# BBB_Headers.net
KiCad netlist of a schematic drawn in Altium Designer
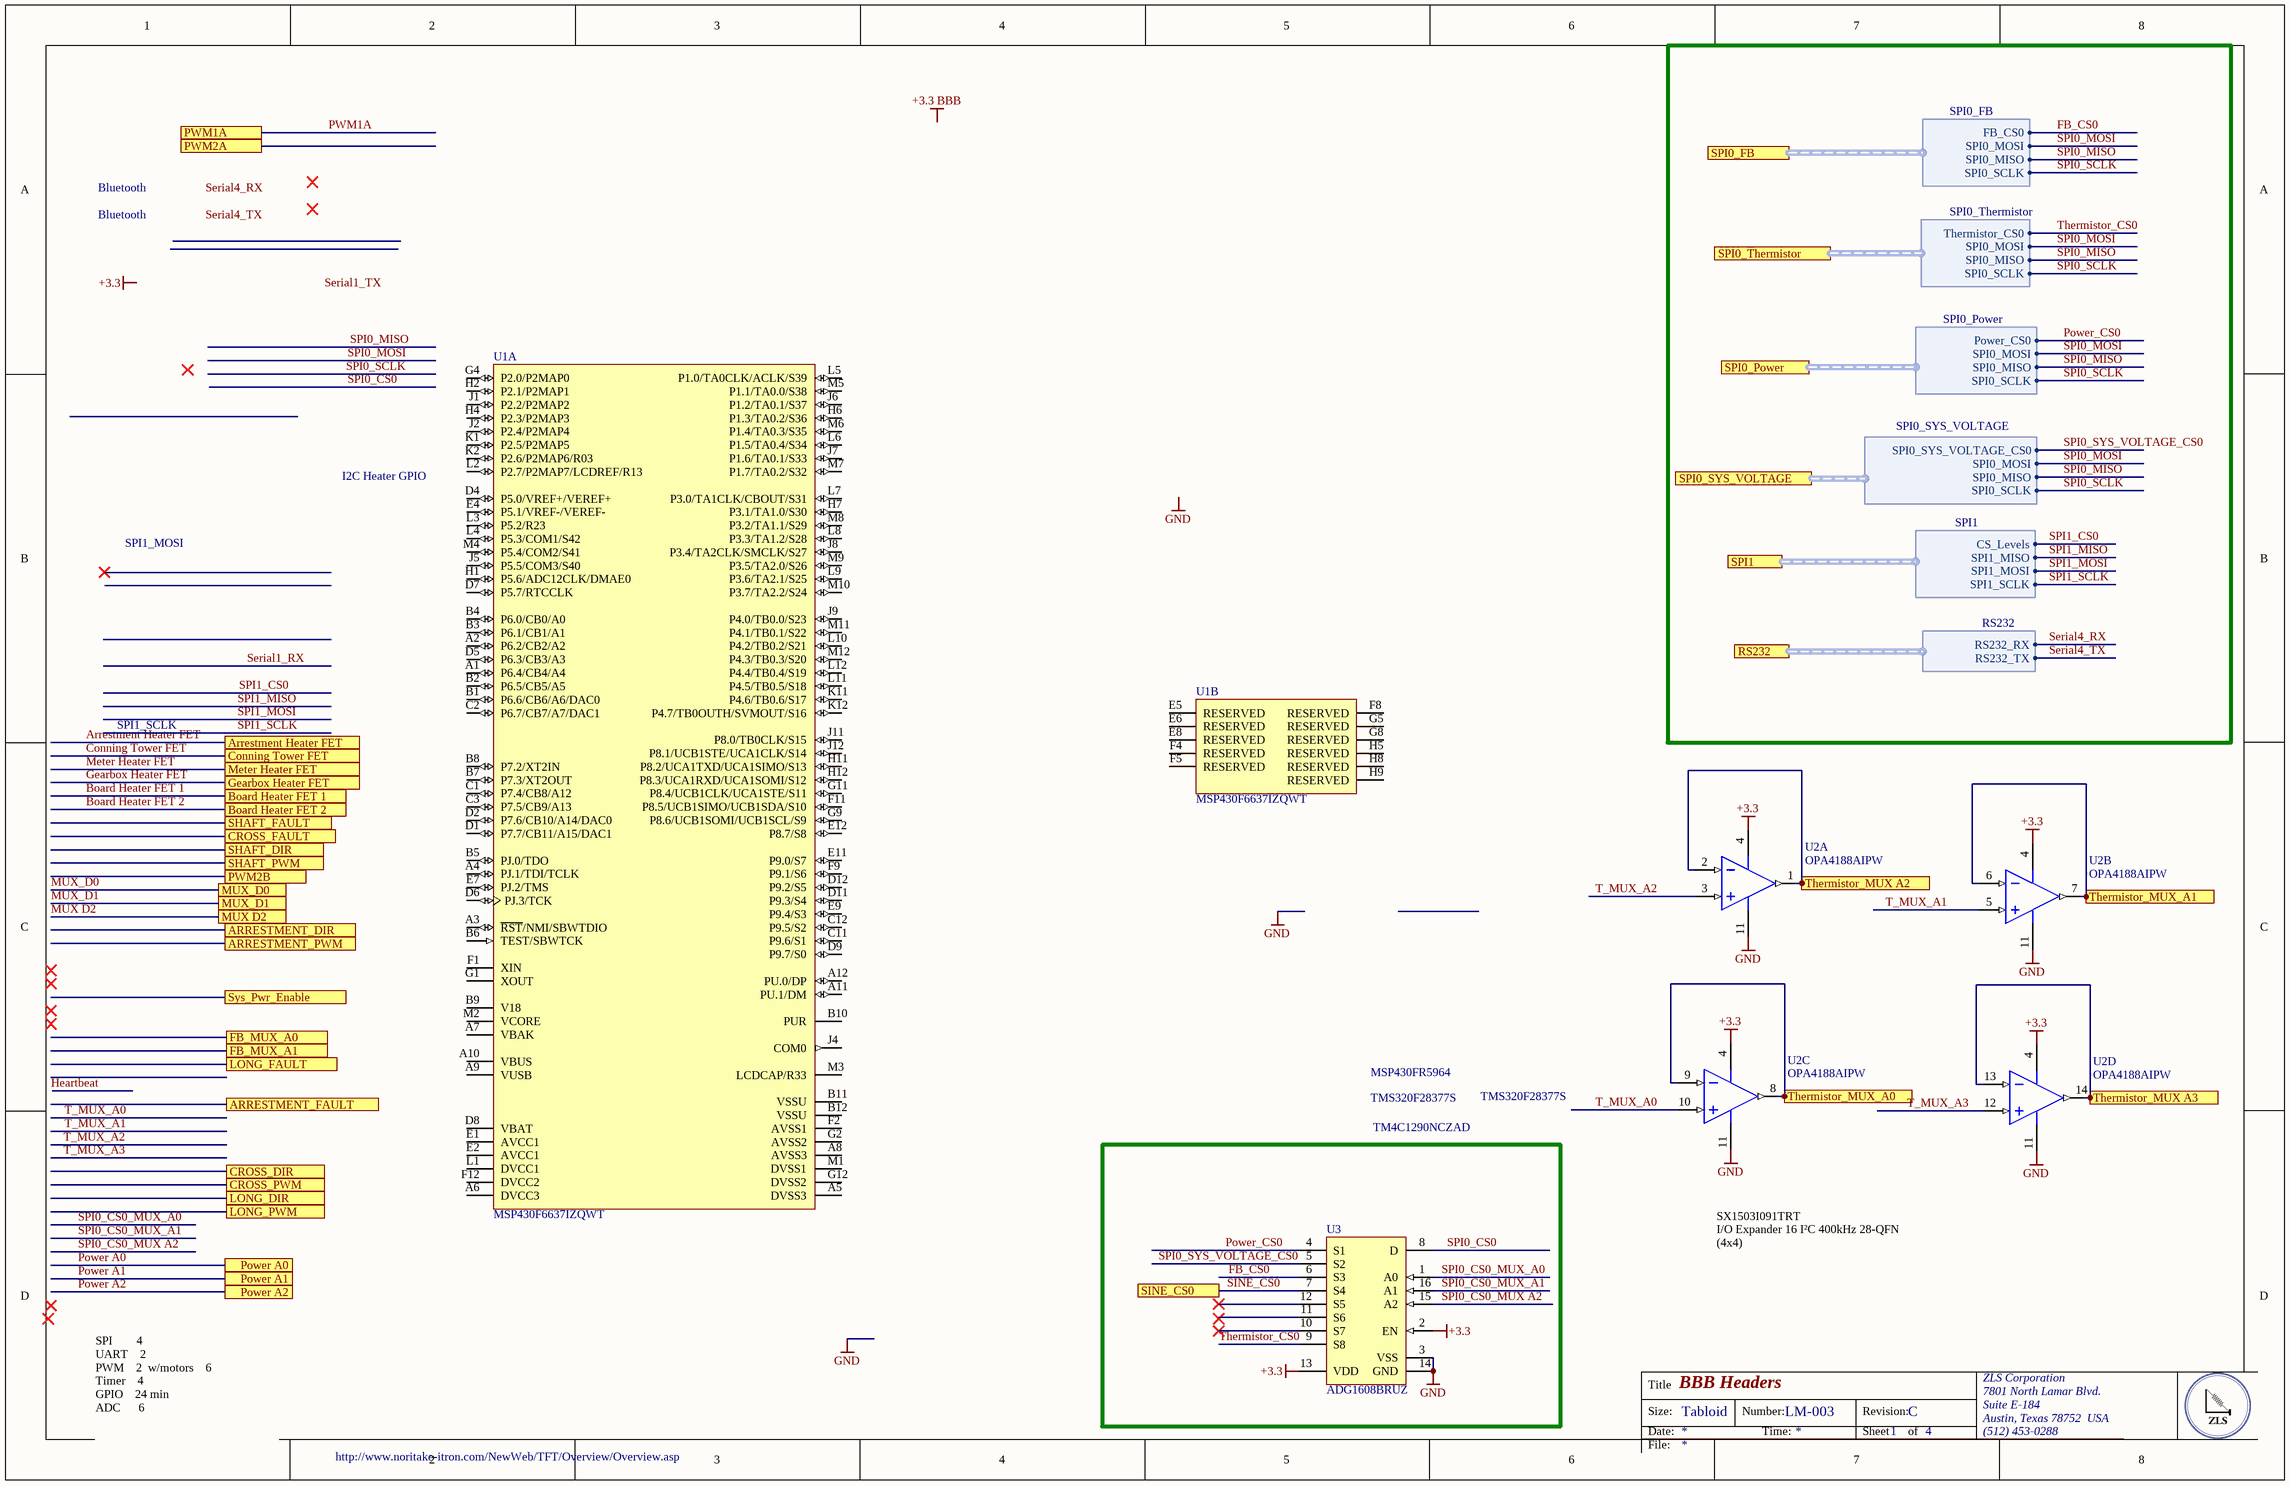
[diagram p0: BBB Headers.SchDoc]

(export (version "E")
  (design (tool "Eeschema 10.0.6"))
  (components
    (comp (ref "U1")
      (value "MSP430F6637IZQWT")
      (footprint "TI-ZQW113")
      (fields (field (name "MANUFACTURER") "Texas Instruments"))
      (libsource (lib "Altium Content Vault") (part "TI-MSP430F663X-ZQW113_A"))
    )
    (comp (ref "U2")
      (value "OPA4188AIPW")
      (footprint "PW0014A_N")
      (fields (field (name "MANUFACTURER") "Texas Instruments"))
      (libsource (lib "Altium Content Vault") (part "TI-OPA4188-PW14"))
    )
    (comp (ref "U3")
      (value "ADG1608BRUZ")
      (footprint "ADI-RU-16_M")
      (description "4.5 Ohm Ron, 8-Channel +/-5 V,+12 V, +5 V and +3.3 V Multiplexer, 16-pin SOP (RU-16), Tube")
      (fields (field (name "MANUFACTURER") "Analog Devices Inc.") (field (name "BASE PART NUMBER") "ADG1608"))
      (libsource (lib "Altium Content Vault") (part "CMP-0793-00136-1"))
    )
  )
  (nets
    (net (code "7") (name "+3.3") (class "Default")
      (node (ref "U2") (pin "4") (pinfunction "V+_4") (pintype "power_in"))
      (node (ref "U3") (pin "13") (pinfunction "VDD_13") (pintype "power_in"))
      (node (ref "U3") (pin "2") (pinfunction "EN_2") (pintype "input"))
    )
    (net (code "19") (name "/FB_CS0") (class "Default")
      (node (ref "U3") (pin "6") (pinfunction "S3_6") (pintype "passive"))
    )
    (net (code "37") (name "/Power_CS0") (class "Default")
      (node (ref "U3") (pin "4") (pinfunction "S1_4") (pintype "passive"))
    )
    (net (code "41") (name "/SINE_CS0") (class "Default")
      (node (ref "U3") (pin "7") (pinfunction "S4_7") (pintype "passive"))
    )
    (net (code "42") (name "/SPI0_CS0") (class "Default")
      (node (ref "U3") (pin "8") (pinfunction "D_8") (pintype "passive"))
    )
    (net (code "43") (name "/SPI0_CS0_MUX A2") (class "Default")
      (node (ref "U3") (pin "15") (pinfunction "A2_15") (pintype "input"))
    )
    (net (code "44") (name "/SPI0_CS0_MUX_A0") (class "Default")
      (node (ref "U3") (pin "1") (pinfunction "A0_1") (pintype "input"))
    )
    (net (code "45") (name "/SPI0_CS0_MUX_A1") (class "Default")
      (node (ref "U3") (pin "16") (pinfunction "A1_16") (pintype "input"))
    )
    (net (code "49") (name "/SPI0_SYS_VOLTAGE_CS0") (class "Default")
      (node (ref "U3") (pin "5") (pinfunction "S2_5") (pintype "passive"))
    )
    (net (code "59") (name "/T_MUX_A0") (class "Default")
      (node (ref "U2") (pin "10") (pinfunction "IN_C+_10") (pintype "input"))
    )
    (net (code "60") (name "/T_MUX_A1") (class "Default")
      (node (ref "U2") (pin "5") (pinfunction "IN_B+_5") (pintype "input"))
    )
    (net (code "61") (name "/T_MUX_A2") (class "Default")
      (node (ref "U2") (pin "3") (pinfunction "IN_A+_3") (pintype "input"))
    )
    (net (code "62") (name "/T_MUX_A3") (class "Default")
      (node (ref "U2") (pin "12") (pinfunction "IN_D+_12") (pintype "input"))
    )
    (net (code "63") (name "/Thermistor_CS0") (class "Default")
      (node (ref "U3") (pin "9") (pinfunction "S8_9") (pintype "passive"))
    )
    (net (code "64") (name "/Thermistor_MUX A2") (class "Default")
      (node (ref "U2") (pin "1") (pinfunction "OUT_A_1") (pintype "output"))
      (node (ref "U2") (pin "2") (pinfunction "IN_A-_2") (pintype "input"))
    )
    (net (code "65") (name "/Thermistor_MUX A3") (class "Default")
      (node (ref "U2") (pin "13") (pinfunction "IN_D-_13") (pintype "input"))
      (node (ref "U2") (pin "14") (pinfunction "OUT_D_14") (pintype "output"))
    )
    (net (code "66") (name "/Thermistor_MUX_A0") (class "Default")
      (node (ref "U2") (pin "8") (pinfunction "OUT_C_8") (pintype "output"))
      (node (ref "U2") (pin "9") (pinfunction "IN_C-_9") (pintype "input"))
    )
    (net (code "67") (name "/Thermistor_MUX_A1") (class "Default")
      (node (ref "U2") (pin "6") (pinfunction "IN_B-_6") (pintype "input"))
      (node (ref "U2") (pin "7") (pinfunction "OUT_B_7") (pintype "output"))
    )
    (net (code "74") (name "GND") (class "Default")
      (node (ref "U2") (pin "11") (pinfunction "V-_11") (pintype "power_in"))
      (node (ref "U3") (pin "14") (pinfunction "GND_14") (pintype "power_in"))
      (node (ref "U3") (pin "3") (pinfunction "VSS_3") (pintype "power_in"))
    )
    (net (code "75") (name "unconnected-(U1A-AVCC1-PadE1)") (class "Default")
      (node (ref "U1") (pin "E1") (pinfunction "AVCC1_E1") (pintype "power_in"))
    )
    (net (code "76") (name "unconnected-(U1A-AVCC1-PadE2)") (class "Default")
      (node (ref "U1") (pin "E2") (pinfunction "AVCC1_E2") (pintype "power_in"))
    )
    (net (code "77") (name "unconnected-(U1A-AVSS1-PadF2)") (class "Default")
      (node (ref "U1") (pin "F2") (pinfunction "AVSS1_F2") (pintype "power_in"))
    )
    (net (code "78") (name "unconnected-(U1A-AVSS2-PadG2)") (class "Default")
      (node (ref "U1") (pin "G2") (pinfunction "AVSS2_G2") (pintype "power_in"))
    )
    (net (code "79") (name "unconnected-(U1A-AVSS3-PadA8)") (class "Default")
      (node (ref "U1") (pin "A8") (pinfunction "AVSS3_A8") (pintype "power_in"))
    )
    (net (code "80") (name "unconnected-(U1A-COM0-PadJ4)") (class "Default")
      (node (ref "U1") (pin "J4") (pinfunction "COM0_J4") (pintype "output"))
    )
    (net (code "81") (name "unconnected-(U1A-DVCC1-PadL1)") (class "Default")
      (node (ref "U1") (pin "L1") (pinfunction "DVCC1_L1") (pintype "power_in"))
    )
    (net (code "82") (name "unconnected-(U1A-DVCC2-PadF12)") (class "Default")
      (node (ref "U1") (pin "F12") (pinfunction "DVCC2_F12") (pintype "power_in"))
    )
    (net (code "83") (name "unconnected-(U1A-DVCC3-PadA6)") (class "Default")
      (node (ref "U1") (pin "A6") (pinfunction "DVCC3_A6") (pintype "power_in"))
    )
    (net (code "84") (name "unconnected-(U1A-DVSS1-PadM1)") (class "Default")
      (node (ref "U1") (pin "M1") (pinfunction "DVSS1_M1") (pintype "power_in"))
    )
    (net (code "85") (name "unconnected-(U1A-DVSS2-PadG12)") (class "Default")
      (node (ref "U1") (pin "G12") (pinfunction "DVSS2_G12") (pintype "power_in"))
    )
    (net (code "86") (name "unconnected-(U1A-DVSS3-PadA5)") (class "Default")
      (node (ref "U1") (pin "A5") (pinfunction "DVSS3_A5") (pintype "power_in"))
    )
    (net (code "87") (name "unconnected-(U1A-LCDCAP{slash}R33-PadM3)") (class "Default")
      (node (ref "U1") (pin "M3") (pinfunction "LCDCAP/R33_M3") (pintype "passive"))
    )
    (net (code "88") (name "unconnected-(U1A-P1.0{slash}TA0CLK{slash}ACLK{slash}S39-PadL5)") (class "Default")
      (node (ref "U1") (pin "L5") (pinfunction "P1.0/TA0CLK/ACLK/S39_L5") (pintype "bidirectional"))
    )
    (net (code "89") (name "unconnected-(U1A-P1.1{slash}TA0.0{slash}S38-PadM5)") (class "Default")
      (node (ref "U1") (pin "M5") (pinfunction "P1.1/TA0.0/S38_M5") (pintype "bidirectional"))
    )
    (net (code "90") (name "unconnected-(U1A-P1.2{slash}TA0.1{slash}S37-PadJ6)") (class "Default")
      (node (ref "U1") (pin "J6") (pinfunction "P1.2/TA0.1/S37_J6") (pintype "bidirectional"))
    )
    (net (code "91") (name "unconnected-(U1A-P1.3{slash}TA0.2{slash}S36-PadH6)") (class "Default")
      (node (ref "U1") (pin "H6") (pinfunction "P1.3/TA0.2/S36_H6") (pintype "bidirectional"))
    )
    (net (code "92") (name "unconnected-(U1A-P1.4{slash}TA0.3{slash}S35-PadM6)") (class "Default")
      (node (ref "U1") (pin "M6") (pinfunction "P1.4/TA0.3/S35_M6") (pintype "bidirectional"))
    )
    (net (code "93") (name "unconnected-(U1A-P1.5{slash}TA0.4{slash}S34-PadL6)") (class "Default")
      (node (ref "U1") (pin "L6") (pinfunction "P1.5/TA0.4/S34_L6") (pintype "bidirectional"))
    )
    (net (code "94") (name "unconnected-(U1A-P1.6{slash}TA0.1{slash}S33-PadJ7)") (class "Default")
      (node (ref "U1") (pin "J7") (pinfunction "P1.6/TA0.1/S33_J7") (pintype "bidirectional"))
    )
    (net (code "95") (name "unconnected-(U1A-P1.7{slash}TA0.2{slash}S32-PadM7)") (class "Default")
      (node (ref "U1") (pin "M7") (pinfunction "P1.7/TA0.2/S32_M7") (pintype "bidirectional"))
    )
    (net (code "96") (name "unconnected-(U1A-P2.0{slash}P2MAP0-PadG4)") (class "Default")
      (node (ref "U1") (pin "G4") (pinfunction "P2.0/P2MAP0_G4") (pintype "bidirectional"))
    )
    (net (code "97") (name "unconnected-(U1A-P2.1{slash}P2MAP1-PadH2)") (class "Default")
      (node (ref "U1") (pin "H2") (pinfunction "P2.1/P2MAP1_H2") (pintype "bidirectional"))
    )
    (net (code "98") (name "unconnected-(U1A-P2.2{slash}P2MAP2-PadJ1)") (class "Default")
      (node (ref "U1") (pin "J1") (pinfunction "P2.2/P2MAP2_J1") (pintype "bidirectional"))
    )
    (net (code "99") (name "unconnected-(U1A-P2.3{slash}P2MAP3-PadH4)") (class "Default")
      (node (ref "U1") (pin "H4") (pinfunction "P2.3/P2MAP3_H4") (pintype "bidirectional"))
    )
    (net (code "100") (name "unconnected-(U1A-P2.4{slash}P2MAP4-PadJ2)") (class "Default")
      (node (ref "U1") (pin "J2") (pinfunction "P2.4/P2MAP4_J2") (pintype "bidirectional"))
    )
    (net (code "101") (name "unconnected-(U1A-P2.5{slash}P2MAP5-PadK1)") (class "Default")
      (node (ref "U1") (pin "K1") (pinfunction "P2.5/P2MAP5_K1") (pintype "bidirectional"))
    )
    (net (code "102") (name "unconnected-(U1A-P2.6{slash}P2MAP6{slash}R03-PadK2)") (class "Default")
      (node (ref "U1") (pin "K2") (pinfunction "P2.6/P2MAP6/R03_K2") (pintype "bidirectional"))
    )
    (net (code "103") (name "unconnected-(U1A-P2.7{slash}P2MAP7{slash}LCDREF{slash}R13-PadL2)") (class "Default")
      (node (ref "U1") (pin "L2") (pinfunction "P2.7/P2MAP7/LCDREF/R13_L2") (pintype "bidirectional"))
    )
    (net (code "104") (name "unconnected-(U1A-P3.0{slash}TA1CLK{slash}CBOUT{slash}S31-PadL7)") (class "Default")
      (node (ref "U1") (pin "L7") (pinfunction "P3.0/TA1CLK/CBOUT/S31_L7") (pintype "bidirectional"))
    )
    (net (code "105") (name "unconnected-(U1A-P3.1{slash}TA1.0{slash}S30-PadH7)") (class "Default")
      (node (ref "U1") (pin "H7") (pinfunction "P3.1/TA1.0/S30_H7") (pintype "bidirectional"))
    )
    (net (code "106") (name "unconnected-(U1A-P3.2{slash}TA1.1{slash}S29-PadM8)") (class "Default")
      (node (ref "U1") (pin "M8") (pinfunction "P3.2/TA1.1/S29_M8") (pintype "bidirectional"))
    )
    (net (code "107") (name "unconnected-(U1A-P3.3{slash}TA1.2{slash}S28-PadL8)") (class "Default")
      (node (ref "U1") (pin "L8") (pinfunction "P3.3/TA1.2/S28_L8") (pintype "bidirectional"))
    )
    (net (code "108") (name "unconnected-(U1A-P3.4{slash}TA2CLK{slash}SMCLK{slash}S27-PadJ8)") (class "Default")
      (node (ref "U1") (pin "J8") (pinfunction "P3.4/TA2CLK/SMCLK/S27_J8") (pintype "bidirectional"))
    )
    (net (code "109") (name "unconnected-(U1A-P3.5{slash}TA2.0{slash}S26-PadM9)") (class "Default")
      (node (ref "U1") (pin "M9") (pinfunction "P3.5/TA2.0/S26_M9") (pintype "bidirectional"))
    )
    (net (code "110") (name "unconnected-(U1A-P3.6{slash}TA2.1{slash}S25-PadL9)") (class "Default")
      (node (ref "U1") (pin "L9") (pinfunction "P3.6/TA2.1/S25_L9") (pintype "bidirectional"))
    )
    (net (code "111") (name "unconnected-(U1A-P3.7{slash}TA2.2{slash}S24-PadM10)") (class "Default")
      (node (ref "U1") (pin "M10") (pinfunction "P3.7/TA2.2/S24_M10") (pintype "bidirectional"))
    )
    (net (code "112") (name "unconnected-(U1A-P4.0{slash}TB0.0{slash}S23-PadJ9)") (class "Default")
      (node (ref "U1") (pin "J9") (pinfunction "P4.0/TB0.0/S23_J9") (pintype "bidirectional"))
    )
    (net (code "113") (name "unconnected-(U1A-P4.1{slash}TB0.1{slash}S22-PadM11)") (class "Default")
      (node (ref "U1") (pin "M11") (pinfunction "P4.1/TB0.1/S22_M11") (pintype "bidirectional"))
    )
    (net (code "114") (name "unconnected-(U1A-P4.2{slash}TB0.2{slash}S21-PadL10)") (class "Default")
      (node (ref "U1") (pin "L10") (pinfunction "P4.2/TB0.2/S21_L10") (pintype "bidirectional"))
    )
    (net (code "115") (name "unconnected-(U1A-P4.3{slash}TB0.3{slash}S20-PadM12)") (class "Default")
      (node (ref "U1") (pin "M12") (pinfunction "P4.3/TB0.3/S20_M12") (pintype "bidirectional"))
    )
    (net (code "116") (name "unconnected-(U1A-P4.4{slash}TB0.4{slash}S19-PadL12)") (class "Default")
      (node (ref "U1") (pin "L12") (pinfunction "P4.4/TB0.4/S19_L12") (pintype "bidirectional"))
    )
    (net (code "117") (name "unconnected-(U1A-P4.5{slash}TB0.5{slash}S18-PadL11)") (class "Default")
      (node (ref "U1") (pin "L11") (pinfunction "P4.5/TB0.5/S18_L11") (pintype "bidirectional"))
    )
    (net (code "118") (name "unconnected-(U1A-P4.6{slash}TB0.6{slash}S17-PadK11)") (class "Default")
      (node (ref "U1") (pin "K11") (pinfunction "P4.6/TB0.6/S17_K11") (pintype "bidirectional"))
    )
    (net (code "119") (name "unconnected-(U1A-P4.7{slash}TB0OUTH{slash}SVMOUT{slash}S16-PadK12)") (class "Default")
      (node (ref "U1") (pin "K12") (pinfunction "P4.7/TB0OUTH/SVMOUT/S16_K12") (pintype "bidirectional"))
    )
    (net (code "120") (name "unconnected-(U1A-P5.0{slash}VREF+{slash}VEREF+-PadD4)") (class "Default")
      (node (ref "U1") (pin "D4") (pinfunction "P5.0/VREF+/VEREF+_D4") (pintype "bidirectional"))
    )
    (net (code "121") (name "unconnected-(U1A-P5.1{slash}VREF-{slash}VEREF--PadE4)") (class "Default")
      (node (ref "U1") (pin "E4") (pinfunction "P5.1/VREF-/VEREF-_E4") (pintype "bidirectional"))
    )
    (net (code "122") (name "unconnected-(U1A-P5.2{slash}R23-PadL3)") (class "Default")
      (node (ref "U1") (pin "L3") (pinfunction "P5.2/R23_L3") (pintype "bidirectional"))
    )
    (net (code "123") (name "unconnected-(U1A-P5.3{slash}COM1{slash}S42-PadL4)") (class "Default")
      (node (ref "U1") (pin "L4") (pinfunction "P5.3/COM1/S42_L4") (pintype "bidirectional"))
    )
    (net (code "124") (name "unconnected-(U1A-P5.4{slash}COM2{slash}S41-PadM4)") (class "Default")
      (node (ref "U1") (pin "M4") (pinfunction "P5.4/COM2/S41_M4") (pintype "bidirectional"))
    )
    (net (code "125") (name "unconnected-(U1A-P5.5{slash}COM3{slash}S40-PadJ5)") (class "Default")
      (node (ref "U1") (pin "J5") (pinfunction "P5.5/COM3/S40_J5") (pintype "bidirectional"))
    )
    (net (code "126") (name "unconnected-(U1A-P5.6{slash}ADC12CLK{slash}DMAE0-PadH1)") (class "Default")
      (node (ref "U1") (pin "H1") (pinfunction "P5.6/ADC12CLK/DMAE0_H1") (pintype "bidirectional"))
    )
    (net (code "127") (name "unconnected-(U1A-P5.7{slash}RTCCLK-PadD7)") (class "Default")
      (node (ref "U1") (pin "D7") (pinfunction "P5.7/RTCCLK_D7") (pintype "bidirectional"))
    )
    (net (code "128") (name "unconnected-(U1A-P6.0{slash}CB0{slash}A0-PadB4)") (class "Default")
      (node (ref "U1") (pin "B4") (pinfunction "P6.0/CB0/A0_B4") (pintype "bidirectional"))
    )
    (net (code "129") (name "unconnected-(U1A-P6.1{slash}CB1{slash}A1-PadB3)") (class "Default")
      (node (ref "U1") (pin "B3") (pinfunction "P6.1/CB1/A1_B3") (pintype "bidirectional"))
    )
    (net (code "130") (name "unconnected-(U1A-P6.2{slash}CB2{slash}A2-PadA2)") (class "Default")
      (node (ref "U1") (pin "A2") (pinfunction "P6.2/CB2/A2_A2") (pintype "bidirectional"))
    )
    (net (code "131") (name "unconnected-(U1A-P6.3{slash}CB3{slash}A3-PadD5)") (class "Default")
      (node (ref "U1") (pin "D5") (pinfunction "P6.3/CB3/A3_D5") (pintype "bidirectional"))
    )
    (net (code "132") (name "unconnected-(U1A-P6.4{slash}CB4{slash}A4-PadA1)") (class "Default")
      (node (ref "U1") (pin "A1") (pinfunction "P6.4/CB4/A4_A1") (pintype "bidirectional"))
    )
    (net (code "133") (name "unconnected-(U1A-P6.5{slash}CB5{slash}A5-PadB2)") (class "Default")
      (node (ref "U1") (pin "B2") (pinfunction "P6.5/CB5/A5_B2") (pintype "bidirectional"))
    )
    (net (code "134") (name "unconnected-(U1A-P6.6{slash}CB6{slash}A6{slash}DAC0-PadB1)") (class "Default")
      (node (ref "U1") (pin "B1") (pinfunction "P6.6/CB6/A6/DAC0_B1") (pintype "bidirectional"))
    )
    (net (code "135") (name "unconnected-(U1A-P6.7{slash}CB7{slash}A7{slash}DAC1-PadC2)") (class "Default")
      (node (ref "U1") (pin "C2") (pinfunction "P6.7/CB7/A7/DAC1_C2") (pintype "bidirectional"))
    )
    (net (code "136") (name "unconnected-(U1A-P7.2{slash}XT2IN-PadB8)") (class "Default")
      (node (ref "U1") (pin "B8") (pinfunction "P7.2/XT2IN_B8") (pintype "bidirectional"))
    )
    (net (code "137") (name "unconnected-(U1A-P7.3{slash}XT2OUT-PadB7)") (class "Default")
      (node (ref "U1") (pin "B7") (pinfunction "P7.3/XT2OUT_B7") (pintype "bidirectional"))
    )
    (net (code "138") (name "unconnected-(U1A-P7.4{slash}CB8{slash}A12-PadC1)") (class "Default")
      (node (ref "U1") (pin "C1") (pinfunction "P7.4/CB8/A12_C1") (pintype "bidirectional"))
    )
    (net (code "139") (name "unconnected-(U1A-P7.5{slash}CB9{slash}A13-PadC3)") (class "Default")
      (node (ref "U1") (pin "C3") (pinfunction "P7.5/CB9/A13_C3") (pintype "bidirectional"))
    )
    (net (code "140") (name "unconnected-(U1A-P7.6{slash}CB10{slash}A14{slash}DAC0-PadD2)") (class "Default")
      (node (ref "U1") (pin "D2") (pinfunction "P7.6/CB10/A14/DAC0_D2") (pintype "bidirectional"))
    )
    (net (code "141") (name "unconnected-(U1A-P7.7{slash}CB11{slash}A15{slash}DAC1-PadD1)") (class "Default")
      (node (ref "U1") (pin "D1") (pinfunction "P7.7/CB11/A15/DAC1_D1") (pintype "bidirectional"))
    )
    (net (code "142") (name "unconnected-(U1A-P8.0{slash}TB0CLK{slash}S15-PadJ11)") (class "Default")
      (node (ref "U1") (pin "J11") (pinfunction "P8.0/TB0CLK/S15_J11") (pintype "bidirectional"))
    )
    (net (code "143") (name "unconnected-(U1A-P8.1{slash}UCB1STE{slash}UCA1CLK{slash}S14-PadJ12)") (class "Default")
      (node (ref "U1") (pin "J12") (pinfunction "P8.1/UCB1STE/UCA1CLK/S14_J12") (pintype "bidirectional"))
    )
    (net (code "144") (name "unconnected-(U1A-P8.2{slash}UCA1TXD{slash}UCA1SIMO{slash}S13-PadH11)") (class "Default")
      (node (ref "U1") (pin "H11") (pinfunction "P8.2/UCA1TXD/UCA1SIMO/S13_H11") (pintype "bidirectional"))
    )
    (net (code "145") (name "unconnected-(U1A-P8.3{slash}UCA1RXD{slash}UCA1SOMI{slash}S12-PadH12)") (class "Default")
      (node (ref "U1") (pin "H12") (pinfunction "P8.3/UCA1RXD/UCA1SOMI/S12_H12") (pintype "bidirectional"))
    )
    (net (code "146") (name "unconnected-(U1A-P8.4{slash}UCB1CLK{slash}UCA1STE{slash}S11-PadG11)") (class "Default")
      (node (ref "U1") (pin "G11") (pinfunction "P8.4/UCB1CLK/UCA1STE/S11_G11") (pintype "bidirectional"))
    )
    (net (code "147") (name "unconnected-(U1A-P8.5{slash}UCB1SIMO{slash}UCB1SDA{slash}S10-PadF11)") (class "Default")
      (node (ref "U1") (pin "F11") (pinfunction "P8.5/UCB1SIMO/UCB1SDA/S10_F11") (pintype "bidirectional"))
    )
    (net (code "148") (name "unconnected-(U1A-P8.6{slash}UCB1SOMI{slash}UCB1SCL{slash}S9-PadG9)") (class "Default")
      (node (ref "U1") (pin "G9") (pinfunction "P8.6/UCB1SOMI/UCB1SCL/S9_G9") (pintype "bidirectional"))
    )
    (net (code "149") (name "unconnected-(U1A-P8.7{slash}S8-PadE12)") (class "Default")
      (node (ref "U1") (pin "E12") (pinfunction "P8.7/S8_E12") (pintype "bidirectional"))
    )
    (net (code "150") (name "unconnected-(U1A-P9.0{slash}S7-PadE11)") (class "Default")
      (node (ref "U1") (pin "E11") (pinfunction "P9.0/S7_E11") (pintype "bidirectional"))
    )
    (net (code "151") (name "unconnected-(U1A-P9.1{slash}S6-PadF9)") (class "Default")
      (node (ref "U1") (pin "F9") (pinfunction "P9.1/S6_F9") (pintype "bidirectional"))
    )
    (net (code "152") (name "unconnected-(U1A-P9.2{slash}S5-PadD12)") (class "Default")
      (node (ref "U1") (pin "D12") (pinfunction "P9.2/S5_D12") (pintype "bidirectional"))
    )
    (net (code "153") (name "unconnected-(U1A-P9.3{slash}S4-PadD11)") (class "Default")
      (node (ref "U1") (pin "D11") (pinfunction "P9.3/S4_D11") (pintype "bidirectional"))
    )
    (net (code "154") (name "unconnected-(U1A-P9.4{slash}S3-PadE9)") (class "Default")
      (node (ref "U1") (pin "E9") (pinfunction "P9.4/S3_E9") (pintype "bidirectional"))
    )
    (net (code "155") (name "unconnected-(U1A-P9.5{slash}S2-PadC12)") (class "Default")
      (node (ref "U1") (pin "C12") (pinfunction "P9.5/S2_C12") (pintype "bidirectional"))
    )
    (net (code "156") (name "unconnected-(U1A-P9.6{slash}S1-PadC11)") (class "Default")
      (node (ref "U1") (pin "C11") (pinfunction "P9.6/S1_C11") (pintype "bidirectional"))
    )
    (net (code "157") (name "unconnected-(U1A-P9.7{slash}S0-PadD9)") (class "Default")
      (node (ref "U1") (pin "D9") (pinfunction "P9.7/S0_D9") (pintype "bidirectional"))
    )
    (net (code "158") (name "unconnected-(U1A-PJ.0{slash}TDO-PadB5)") (class "Default")
      (node (ref "U1") (pin "B5") (pinfunction "PJ.0/TDO_B5") (pintype "bidirectional"))
    )
    (net (code "159") (name "unconnected-(U1A-PJ.1{slash}TDI{slash}TCLK-PadA4)") (class "Default")
      (node (ref "U1") (pin "A4") (pinfunction "PJ.1/TDI/TCLK_A4") (pintype "bidirectional"))
    )
    (net (code "160") (name "unconnected-(U1A-PJ.2{slash}TMS-PadE7)") (class "Default")
      (node (ref "U1") (pin "E7") (pinfunction "PJ.2/TMS_E7") (pintype "bidirectional"))
    )
    (net (code "161") (name "unconnected-(U1A-PJ.3{slash}TCK-PadD6)") (class "Default")
      (node (ref "U1") (pin "D6") (pinfunction "PJ.3/TCK_D6") (pintype "bidirectional"))
    )
    (net (code "162") (name "unconnected-(U1A-PU.0{slash}DP-PadA12)") (class "Default")
      (node (ref "U1") (pin "A12") (pinfunction "PU.0/DP_A12") (pintype "bidirectional"))
    )
    (net (code "163") (name "unconnected-(U1A-PU.1{slash}DM-PadA11)") (class "Default")
      (node (ref "U1") (pin "A11") (pinfunction "PU.1/DM_A11") (pintype "bidirectional"))
    )
    (net (code "164") (name "unconnected-(U1A-PUR-PadB10)") (class "Default")
      (node (ref "U1") (pin "B10") (pinfunction "PUR_B10") (pintype "passive"))
    )
    (net (code "165") (name "unconnected-(U1A-TEST{slash}SBWTCK-PadB6)") (class "Default")
      (node (ref "U1") (pin "B6") (pinfunction "TEST/SBWTCK_B6") (pintype "input"))
    )
    (net (code "166") (name "unconnected-(U1A-V18-PadB9)") (class "Default")
      (node (ref "U1") (pin "B9") (pinfunction "V18_B9") (pintype "passive"))
    )
    (net (code "167") (name "unconnected-(U1A-VBAK-PadA7)") (class "Default")
      (node (ref "U1") (pin "A7") (pinfunction "VBAK_A7") (pintype "passive"))
    )
    (net (code "168") (name "unconnected-(U1A-VBAT-PadD8)") (class "Default")
      (node (ref "U1") (pin "D8") (pinfunction "VBAT_D8") (pintype "power_in"))
    )
    (net (code "169") (name "unconnected-(U1A-VBUS-PadA10)") (class "Default")
      (node (ref "U1") (pin "A10") (pinfunction "VBUS_A10") (pintype "power_in"))
    )
    (net (code "170") (name "unconnected-(U1A-VCORE-PadM2)") (class "Default")
      (node (ref "U1") (pin "M2") (pinfunction "VCORE_M2") (pintype "passive"))
    )
    (net (code "171") (name "unconnected-(U1A-VSSU-PadB11)") (class "Default")
      (node (ref "U1") (pin "B11") (pinfunction "VSSU_B11") (pintype "power_in"))
    )
    (net (code "172") (name "unconnected-(U1A-VSSU-PadB12)") (class "Default")
      (node (ref "U1") (pin "B12") (pinfunction "VSSU_B12") (pintype "power_in"))
    )
    (net (code "173") (name "unconnected-(U1A-VUSB-PadA9)") (class "Default")
      (node (ref "U1") (pin "A9") (pinfunction "VUSB_A9") (pintype "power_in"))
    )
    (net (code "174") (name "unconnected-(U1A-XIN-PadF1)") (class "Default")
      (node (ref "U1") (pin "F1") (pinfunction "XIN_F1") (pintype "passive"))
    )
    (net (code "175") (name "unconnected-(U1A-XOUT-PadG1)") (class "Default")
      (node (ref "U1") (pin "G1") (pinfunction "XOUT_G1") (pintype "passive"))
    )
    (net (code "176") (name "unconnected-(U1A-~{RST}{slash}NMI{slash}SBWTDIO-PadA3)") (class "Default")
      (node (ref "U1") (pin "A3") (pinfunction "~{RST}/NMI/SBWTDIO_A3") (pintype "bidirectional"))
    )
    (net (code "177") (name "unconnected-(U1B-RESERVED-PadE5)") (class "Default")
      (node (ref "U1") (pin "E5") (pinfunction "RESERVED_E5") (pintype "passive"))
    )
    (net (code "178") (name "unconnected-(U1B-RESERVED-PadE6)") (class "Default")
      (node (ref "U1") (pin "E6") (pinfunction "RESERVED_E6") (pintype "passive"))
    )
    (net (code "179") (name "unconnected-(U1B-RESERVED-PadE8)") (class "Default")
      (node (ref "U1") (pin "E8") (pinfunction "RESERVED_E8") (pintype "passive"))
    )
    (net (code "180") (name "unconnected-(U1B-RESERVED-PadF4)") (class "Default")
      (node (ref "U1") (pin "F4") (pinfunction "RESERVED_F4") (pintype "passive"))
    )
    (net (code "181") (name "unconnected-(U1B-RESERVED-PadF5)") (class "Default")
      (node (ref "U1") (pin "F5") (pinfunction "RESERVED_F5") (pintype "passive"))
    )
    (net (code "182") (name "unconnected-(U1B-RESERVED-PadF8)") (class "Default")
      (node (ref "U1") (pin "F8") (pinfunction "RESERVED_F8") (pintype "passive"))
    )
    (net (code "183") (name "unconnected-(U1B-RESERVED-PadG5)") (class "Default")
      (node (ref "U1") (pin "G5") (pinfunction "RESERVED_G5") (pintype "passive"))
    )
    (net (code "184") (name "unconnected-(U1B-RESERVED-PadG8)") (class "Default")
      (node (ref "U1") (pin "G8") (pinfunction "RESERVED_G8") (pintype "passive"))
    )
    (net (code "185") (name "unconnected-(U1B-RESERVED-PadH5)") (class "Default")
      (node (ref "U1") (pin "H5") (pinfunction "RESERVED_H5") (pintype "passive"))
    )
    (net (code "186") (name "unconnected-(U1B-RESERVED-PadH8)") (class "Default")
      (node (ref "U1") (pin "H8") (pinfunction "RESERVED_H8") (pintype "passive"))
    )
    (net (code "187") (name "unconnected-(U1B-RESERVED-PadH9)") (class "Default")
      (node (ref "U1") (pin "H9") (pinfunction "RESERVED_H9") (pintype "passive"))
    )
    (net (code "188") (name "unconnected-(U3-S5-Pad12)") (class "Default")
      (node (ref "U3") (pin "12") (pinfunction "S5_12") (pintype "passive+no_connect"))
    )
    (net (code "189") (name "unconnected-(U3-S6-Pad11)") (class "Default")
      (node (ref "U3") (pin "11") (pinfunction "S6_11") (pintype "passive"))
    )
    (net (code "190") (name "unconnected-(U3-S7-Pad10)") (class "Default")
      (node (ref "U3") (pin "10") (pinfunction "S7_10") (pintype "passive+no_connect"))
    )
  )
)
